# FootSensorV1.net
KiCad netlist of a schematic drawn in EAGLE
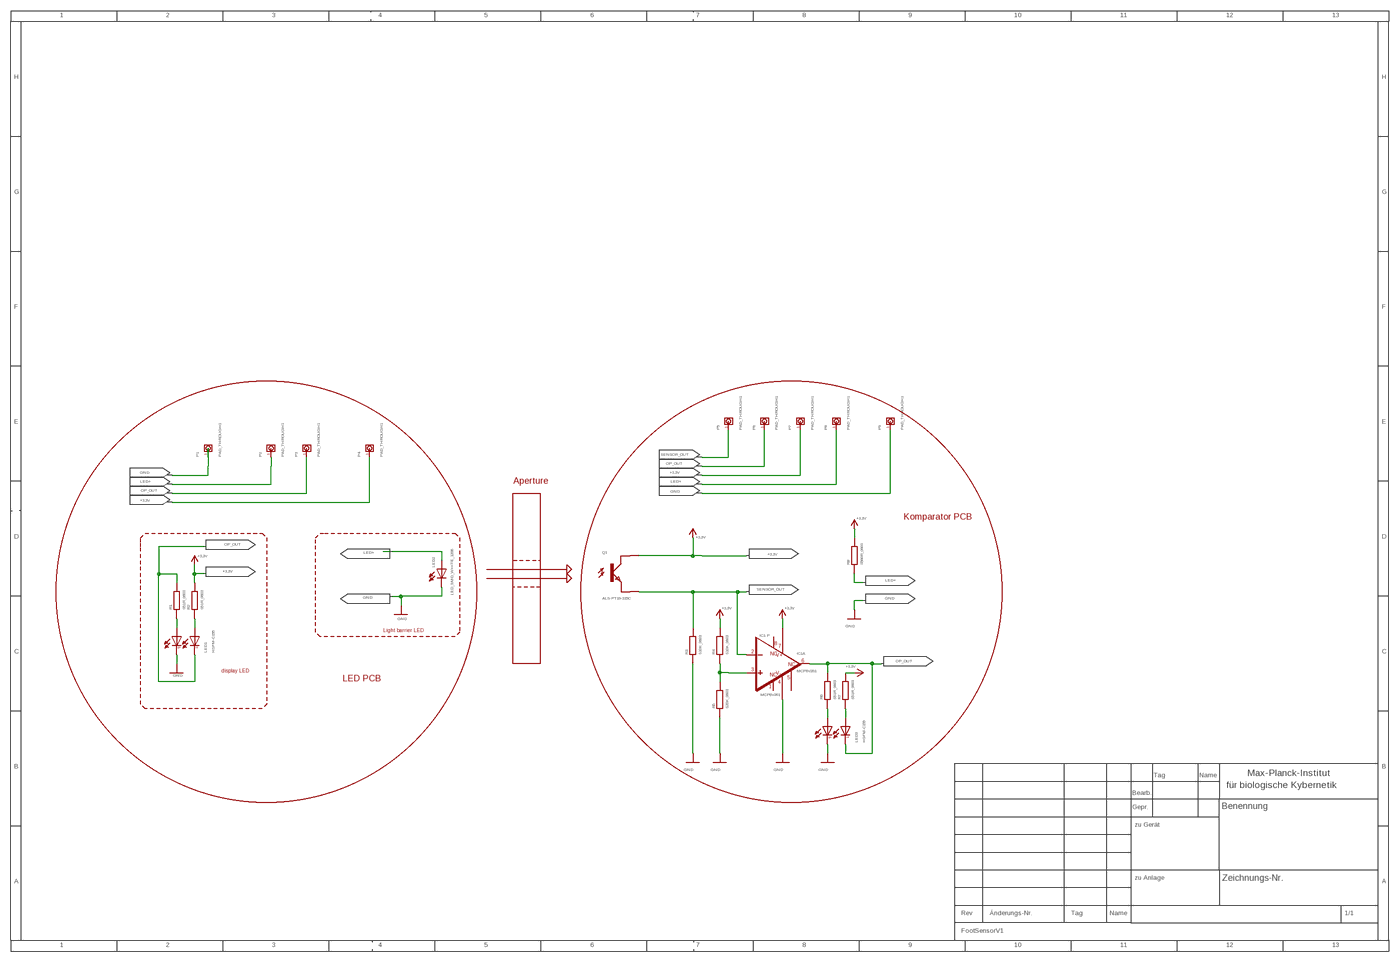
[diagram p0: schematic, sheet 1, overview]
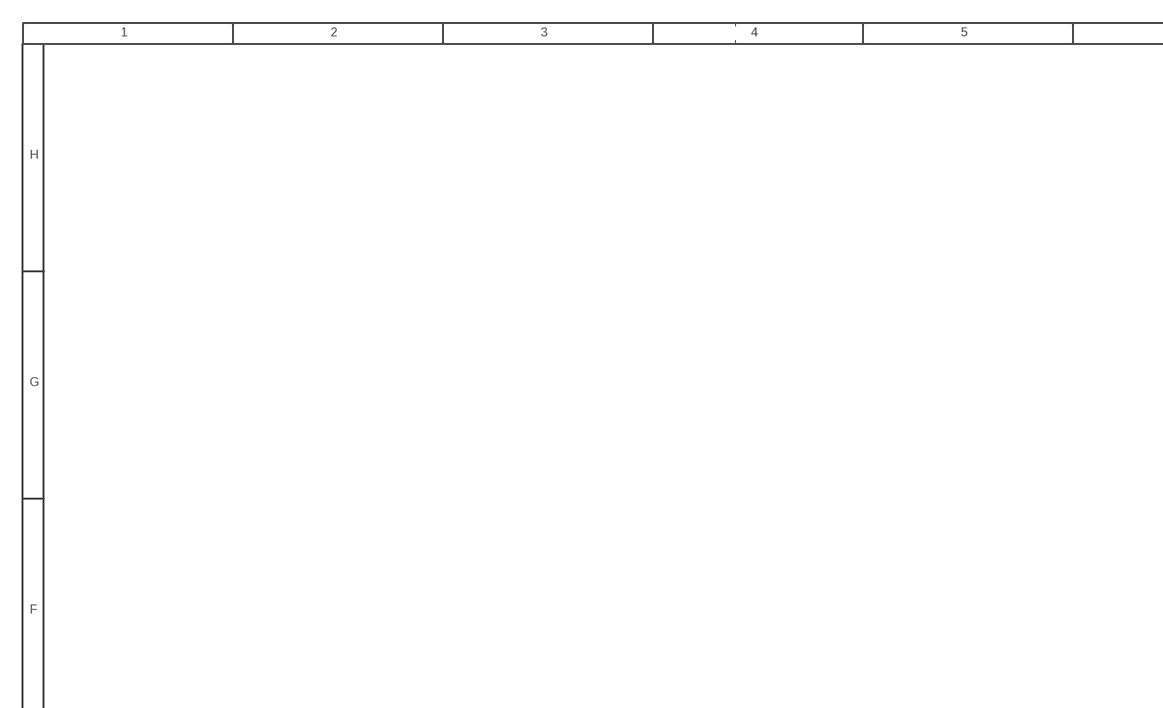
[diagram p1: schematic, sheet 1, part 1 of 4]
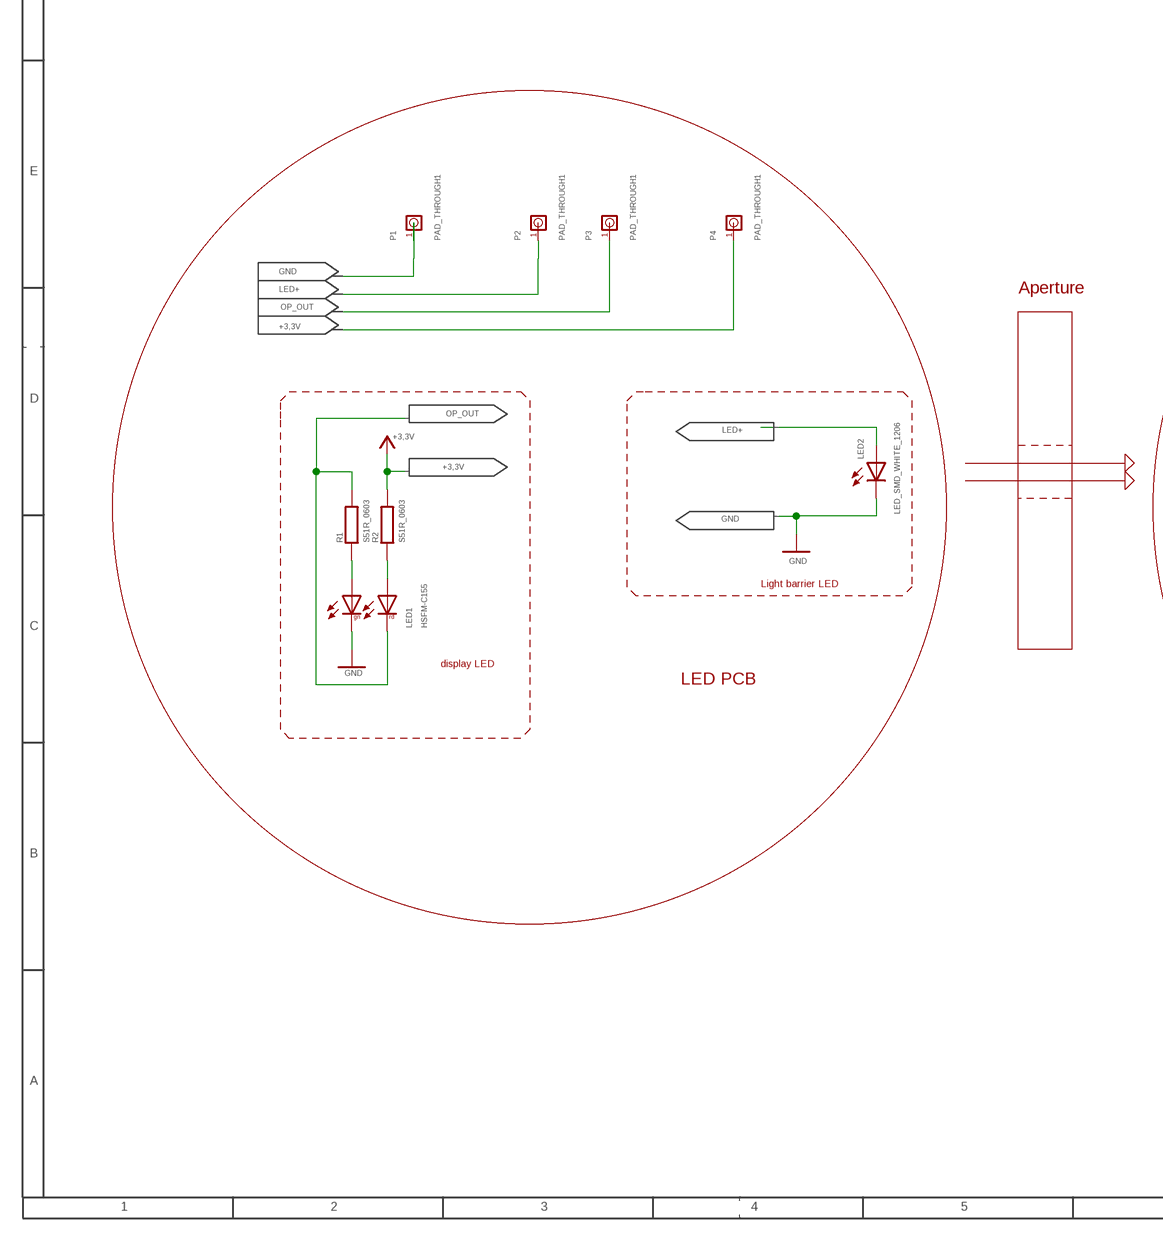
[diagram p2: schematic, sheet 1, part 2 of 4]
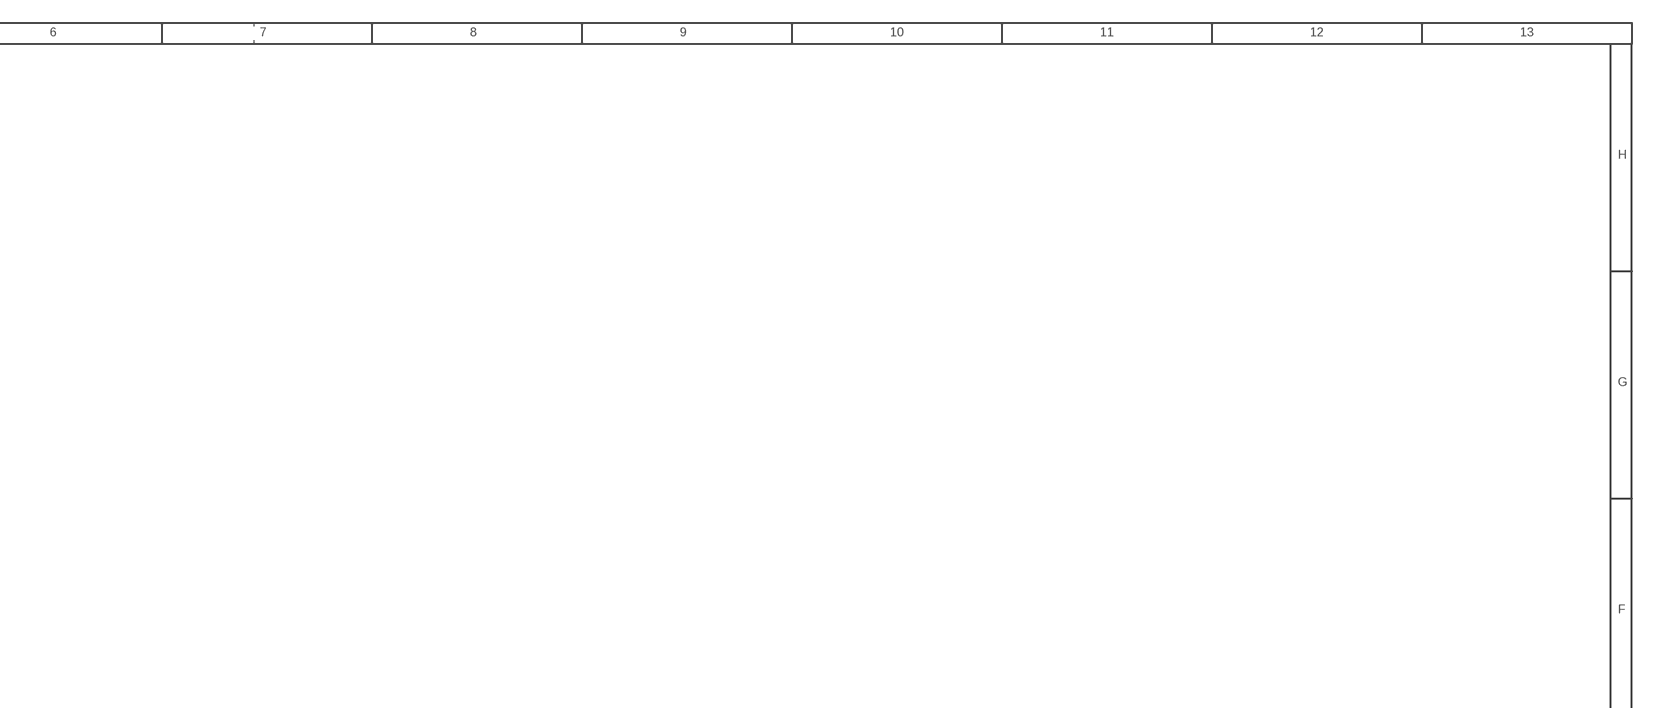
[diagram p3: schematic, sheet 1, part 3 of 4]
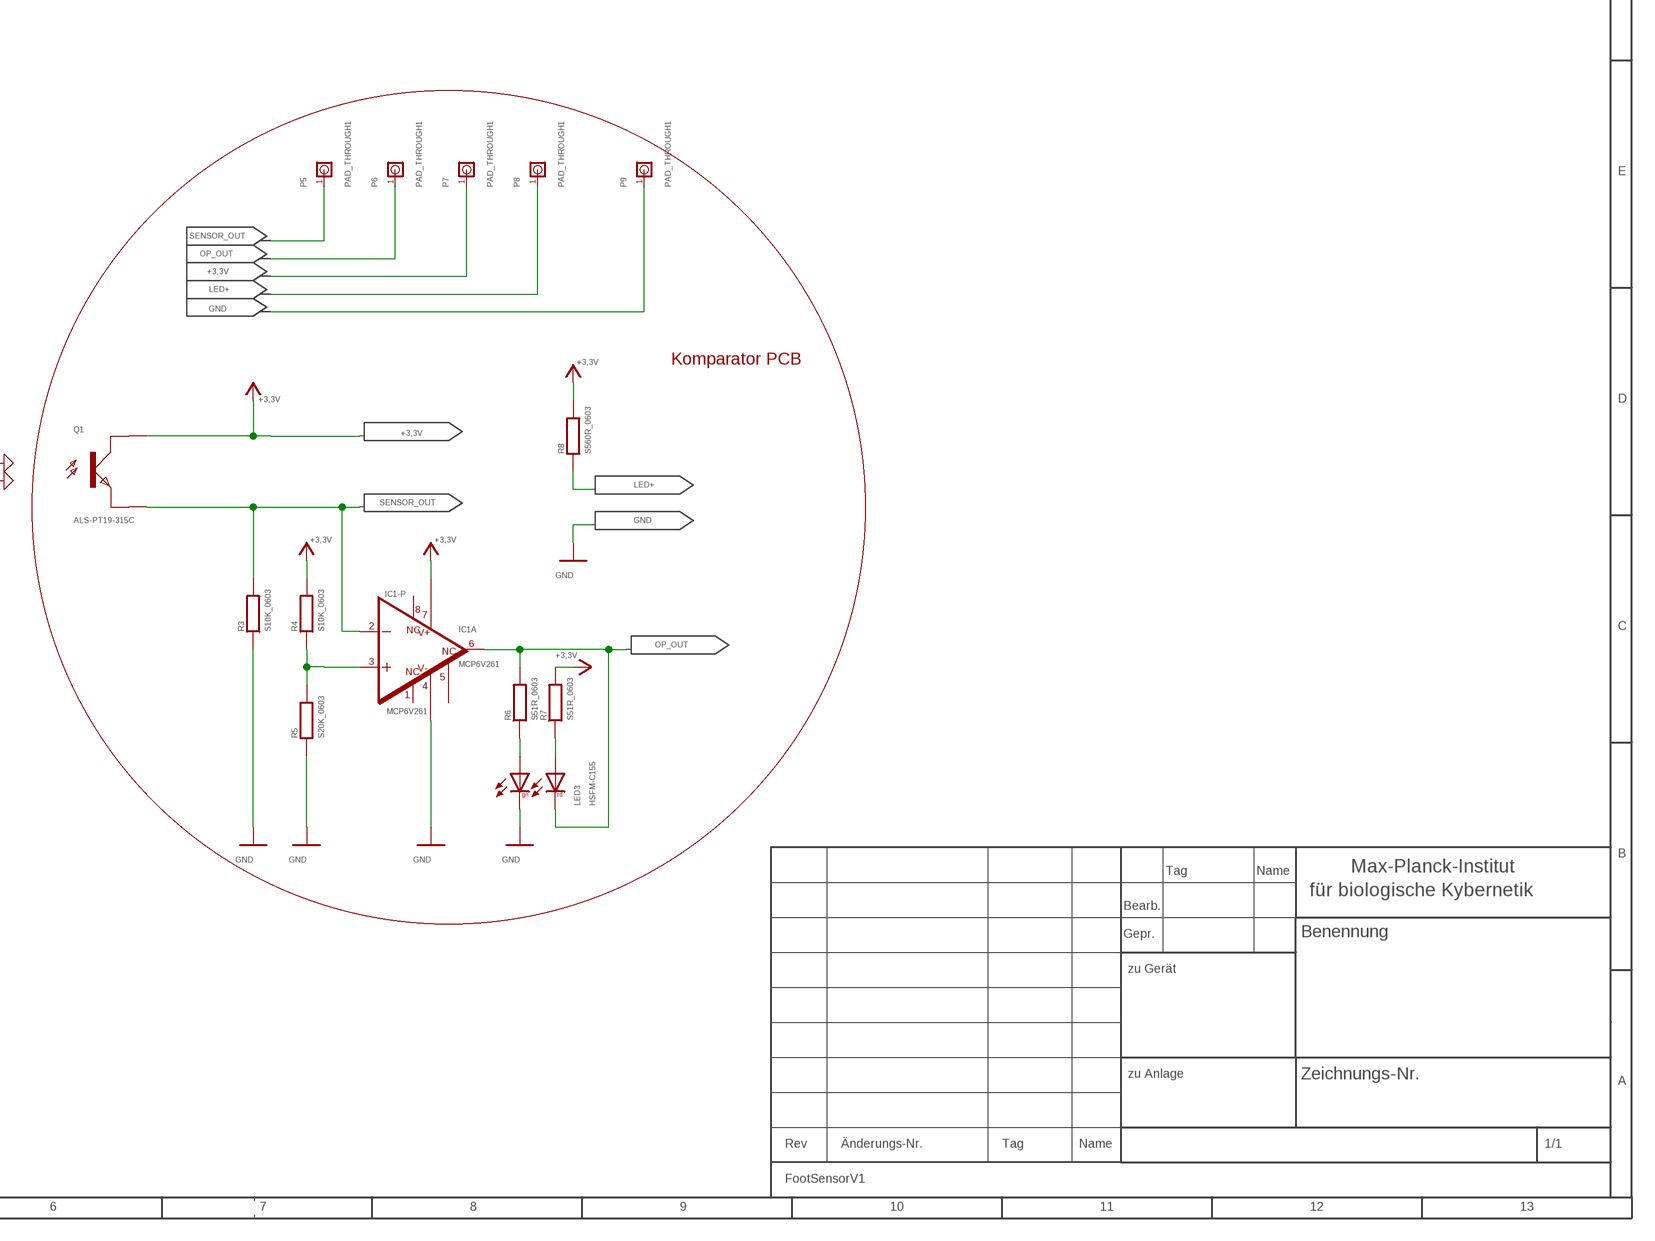
[diagram p4: schematic, sheet 1, part 4 of 4]

(export (version "E")
  (design (tool "Eeschema 10.0.6"))
  (components
    (comp (ref "IC1")
      (value "MCP6V261")
      (footprint "eagle-import:MSOP8")
      (libsource (lib "eagle-import") (part "MCP6V261"))
    )
    (comp (ref "LED1")
      (value "HSFM-C155")
      (footprint "eagle-import:3225")
      (libsource (lib "eagle-import") (part "HSFM-C155"))
    )
    (comp (ref "LED2")
      (value "LED_SMD_WHITE_1206")
      (footprint "eagle-import:1206C")
      (libsource (lib "eagle-import") (part "LED_SMD_WHITE_1206"))
    )
    (comp (ref "LED3")
      (value "HSFM-C155")
      (footprint "eagle-import:3225")
      (libsource (lib "eagle-import") (part "HSFM-C155"))
    )
    (comp (ref "P1")
      (value "PAD_THROUGH1")
      (footprint "eagle-import:PAD_TH_056X055")
      (libsource (lib "eagle-import") (part "PAD_THROUGH1"))
    )
    (comp (ref "P2")
      (value "PAD_THROUGH1")
      (footprint "eagle-import:PAD_TH_056X055")
      (libsource (lib "eagle-import") (part "PAD_THROUGH1"))
    )
    (comp (ref "P3")
      (value "PAD_THROUGH1")
      (footprint "eagle-import:PAD_TH_056X055")
      (libsource (lib "eagle-import") (part "PAD_THROUGH1"))
    )
    (comp (ref "P4")
      (value "PAD_THROUGH1")
      (footprint "eagle-import:PAD_TH_056X055")
      (libsource (lib "eagle-import") (part "PAD_THROUGH1"))
    )
    (comp (ref "P5")
      (value "PAD_THROUGH1")
      (footprint "eagle-import:PAD_TH_056X055")
      (libsource (lib "eagle-import") (part "PAD_THROUGH1"))
    )
    (comp (ref "P6")
      (value "PAD_THROUGH1")
      (footprint "eagle-import:PAD_TH_056X055")
      (libsource (lib "eagle-import") (part "PAD_THROUGH1"))
    )
    (comp (ref "P7")
      (value "PAD_THROUGH1")
      (footprint "eagle-import:PAD_TH_056X055")
      (libsource (lib "eagle-import") (part "PAD_THROUGH1"))
    )
    (comp (ref "P8")
      (value "PAD_THROUGH1")
      (footprint "eagle-import:PAD_TH_056X055")
      (libsource (lib "eagle-import") (part "PAD_THROUGH1"))
    )
    (comp (ref "P9")
      (value "PAD_THROUGH1")
      (footprint "eagle-import:PAD_TH_056X055")
      (libsource (lib "eagle-import") (part "PAD_THROUGH1"))
    )
    (comp (ref "Q1")
      (value "ALS-PT19-315C")
      (footprint "eagle-import:FOTOTRANSISTOR")
      (libsource (lib "eagle-import") (part "ALS-PT19-315C"))
    )
    (comp (ref "R1")
      (value "S51R_0603")
      (footprint "eagle-import:0603R")
      (libsource (lib "eagle-import") (part "S51R_0603"))
    )
    (comp (ref "R2")
      (value "S51R_0603")
      (footprint "eagle-import:0603R")
      (libsource (lib "eagle-import") (part "S51R_0603"))
    )
    (comp (ref "R3")
      (value "S10K_0603")
      (footprint "eagle-import:0603R")
      (libsource (lib "eagle-import") (part "S10K_0603"))
    )
    (comp (ref "R4")
      (value "S10K_0603")
      (footprint "eagle-import:0603R")
      (libsource (lib "eagle-import") (part "S10K_0603"))
    )
    (comp (ref "R5")
      (value "S20K_0603")
      (footprint "eagle-import:0603R")
      (libsource (lib "eagle-import") (part "S20K_0603"))
    )
    (comp (ref "R6")
      (value "S51R_0603")
      (footprint "eagle-import:0603R")
      (libsource (lib "eagle-import") (part "S51R_0603"))
    )
    (comp (ref "R7")
      (value "S51R_0603")
      (footprint "eagle-import:0603R")
      (libsource (lib "eagle-import") (part "S51R_0603"))
    )
    (comp (ref "R8")
      (value "S560R_0603")
      (footprint "eagle-import:0603R")
      (libsource (lib "eagle-import") (part "S560R_0603"))
    )
  )
  (nets
    (net (code "1") (name "+3,3V") (class "Default")
      (node (ref "IC1") (pin "7") (pinfunction "7_7") (pintype "bidirectional"))
      (node (ref "P4") (pin "P$1") (pinfunction "1_P$1") (pintype "passive"))
      (node (ref "P7") (pin "P$1") (pinfunction "1_P$1") (pintype "passive"))
      (node (ref "Q1") (pin "1") (pinfunction "C_1") (pintype "bidirectional"))
      (node (ref "R2") (pin "P$2") (pinfunction "2_P$2") (pintype "passive"))
      (node (ref "R4") (pin "P$2") (pinfunction "2_P$2") (pintype "passive"))
      (node (ref "R7") (pin "P$2") (pinfunction "2_P$2") (pintype "passive"))
      (node (ref "R8") (pin "P$2") (pinfunction "2_P$2") (pintype "passive"))
    )
    (net (code "2") (name "/LED+") (class "Default")
      (node (ref "LED2") (pin "+") (pinfunction "A1_+") (pintype "passive"))
      (node (ref "P2") (pin "P$1") (pinfunction "1_P$1") (pintype "passive"))
      (node (ref "P8") (pin "P$1") (pinfunction "1_P$1") (pintype "passive"))
      (node (ref "R8") (pin "P$1") (pinfunction "1_P$1") (pintype "passive"))
    )
    (net (code "3") (name "/OP_OUT") (class "Default")
      (node (ref "IC1") (pin "6") (pinfunction "6_6") (pintype "output"))
      (node (ref "LED1") (pin "4") (pinfunction "4_4") (pintype "passive"))
      (node (ref "LED3") (pin "4") (pinfunction "4_4") (pintype "passive"))
      (node (ref "P3") (pin "P$1") (pinfunction "1_P$1") (pintype "passive"))
      (node (ref "P6") (pin "P$1") (pinfunction "1_P$1") (pintype "passive"))
      (node (ref "R1") (pin "P$2") (pinfunction "2_P$2") (pintype "passive"))
      (node (ref "R6") (pin "P$2") (pinfunction "2_P$2") (pintype "passive"))
    )
    (net (code "4") (name "/SENSOR_OUT") (class "Default")
      (node (ref "IC1") (pin "2") (pinfunction "2_2") (pintype "input"))
      (node (ref "P5") (pin "P$1") (pinfunction "1_P$1") (pintype "passive"))
      (node (ref "Q1") (pin "2") (pinfunction "E_2") (pintype "bidirectional"))
      (node (ref "R3") (pin "P$2") (pinfunction "2_P$2") (pintype "passive"))
    )
    (net (code "5") (name "GND") (class "Default")
      (node (ref "IC1") (pin "4") (pinfunction "4_4") (pintype "bidirectional"))
      (node (ref "LED1") (pin "2") (pinfunction "2_2") (pintype "passive"))
      (node (ref "LED2") (pin "-") (pinfunction "C1_-") (pintype "passive"))
      (node (ref "LED3") (pin "2") (pinfunction "2_2") (pintype "passive"))
      (node (ref "P1") (pin "P$1") (pinfunction "1_P$1") (pintype "passive"))
      (node (ref "P9") (pin "P$1") (pinfunction "1_P$1") (pintype "passive"))
      (node (ref "R3") (pin "P$1") (pinfunction "1_P$1") (pintype "passive"))
      (node (ref "R5") (pin "P$1") (pinfunction "1_P$1") (pintype "passive"))
    )
    (net (code "6") (name "Net-(R1-1)") (class "Default")
      (node (ref "LED1") (pin "1") (pinfunction "1_1") (pintype "passive"))
      (node (ref "R1") (pin "P$1") (pinfunction "1_P$1") (pintype "passive"))
    )
    (net (code "7") (name "Net-(R2-1)") (class "Default")
      (node (ref "LED1") (pin "3") (pinfunction "3_3") (pintype "passive"))
      (node (ref "R2") (pin "P$1") (pinfunction "1_P$1") (pintype "passive"))
    )
    (net (code "8") (name "Net-(R4-1)") (class "Default")
      (node (ref "IC1") (pin "3") (pinfunction "3_3") (pintype "input"))
      (node (ref "R4") (pin "P$1") (pinfunction "1_P$1") (pintype "passive"))
      (node (ref "R5") (pin "P$2") (pinfunction "2_P$2") (pintype "passive"))
    )
    (net (code "9") (name "Net-(R6-1)") (class "Default")
      (node (ref "LED3") (pin "1") (pinfunction "1_1") (pintype "passive"))
      (node (ref "R6") (pin "P$1") (pinfunction "1_P$1") (pintype "passive"))
    )
    (net (code "10") (name "Net-(R7-1)") (class "Default")
      (node (ref "LED3") (pin "3") (pinfunction "3_3") (pintype "passive"))
      (node (ref "R7") (pin "P$1") (pinfunction "1_P$1") (pintype "passive"))
    )
    (net (code "11") (name "unconnected-(IC1-Pad1)") (class "Default")
      (node (ref "IC1") (pin "1") (pinfunction "1_1") (pintype "bidirectional"))
    )
    (net (code "12") (name "unconnected-(IC1-Pad5)") (class "Default")
      (node (ref "IC1") (pin "5") (pinfunction "5_5") (pintype "bidirectional"))
    )
    (net (code "13") (name "unconnected-(IC1-Pad8)") (class "Default")
      (node (ref "IC1") (pin "8") (pinfunction "8_8") (pintype "bidirectional"))
    )
  )
)
